# ICAN-7006-MCU.net
KiCad netlist of a schematic drawn in Altium Designer
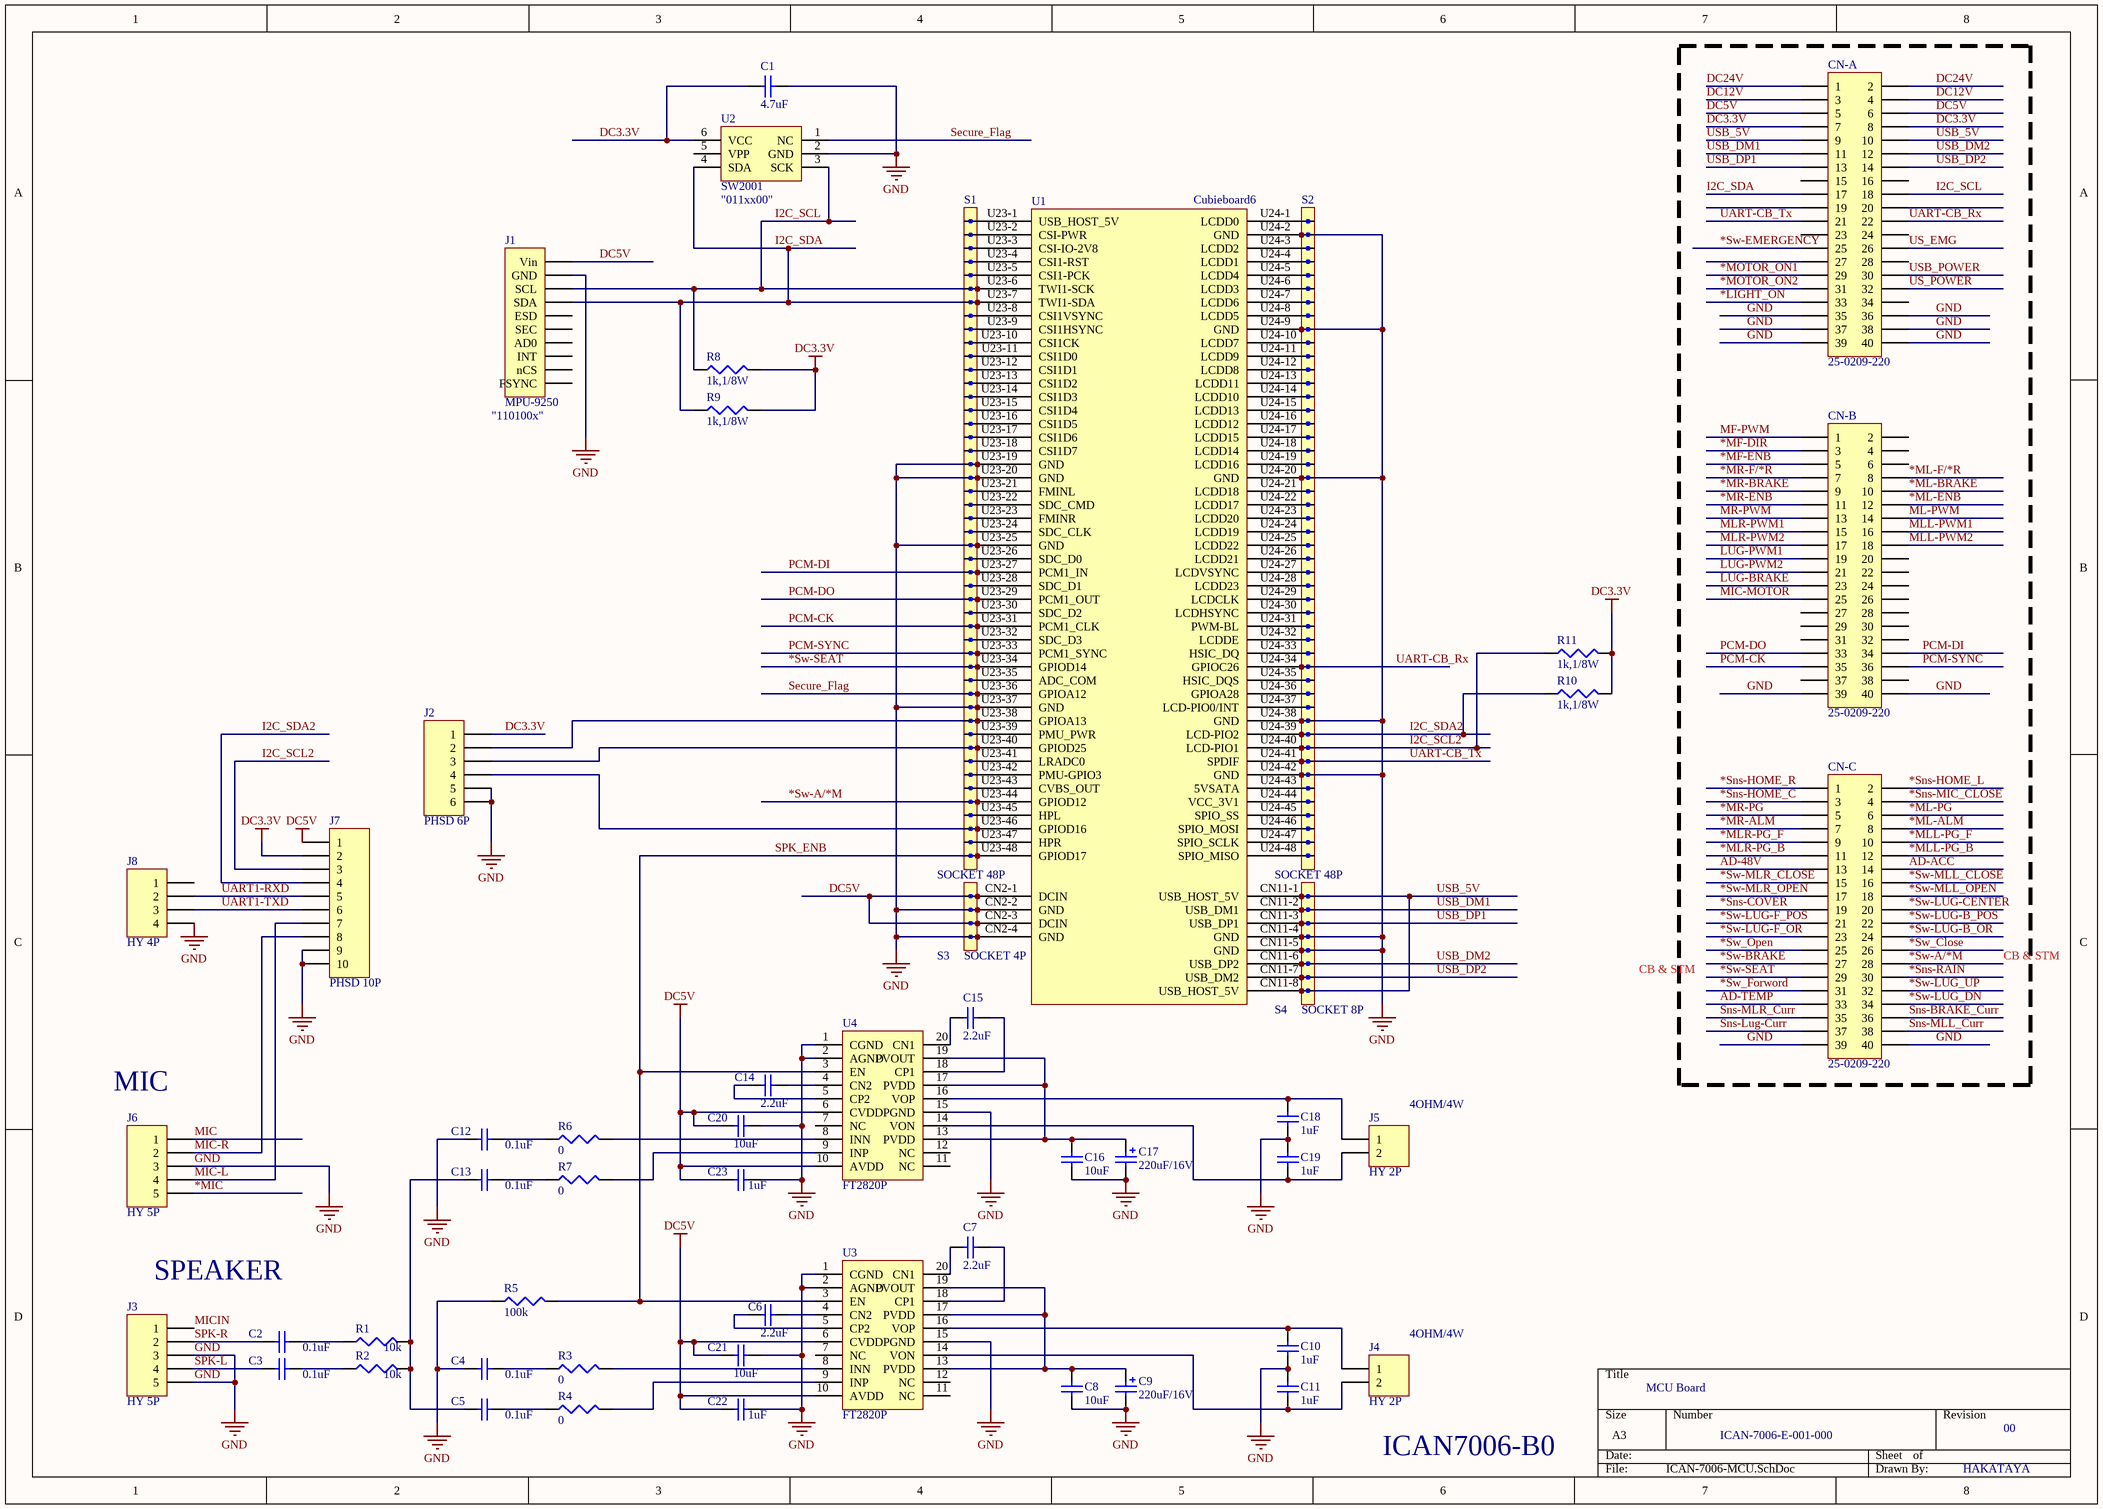
[diagram p0: ICAN-7006-MCU.SchDoc]

(export (version "E")
  (design (tool "Eeschema 10.0.6"))
  (components
    (comp (ref "C1")
      (value "4.7uF")
      (footprint "HAKATAYA:[0805]2012")
      (description "Capacitor")
      (fields (field (name "PUBLISHER") "Altium Limited"))
      (libsource (lib "Miscellaneous Devices") (part "Cap"))
    )
    (comp (ref "C2")
      (value "0.1uF")
      (footprint "[0805]2012")
      (description "Capacitor")
      (fields (field (name "PUBLISHER") "Altium Limited"))
      (libsource (lib "Miscellaneous Devices") (part "Cap Semi"))
    )
    (comp (ref "C3")
      (value "0.1uF")
      (footprint "[0805]2012")
      (description "Capacitor")
      (fields (field (name "PUBLISHER") "Altium Limited"))
      (libsource (lib "Miscellaneous Devices") (part "Cap Semi"))
    )
    (comp (ref "C4")
      (value "0.1uF")
      (footprint "[0805]2012")
      (description "Capacitor")
      (fields (field (name "PUBLISHER") "Altium Limited"))
      (libsource (lib "Miscellaneous Devices") (part "Cap Semi"))
    )
    (comp (ref "C5")
      (value "0.1uF")
      (footprint "[0805]2012")
      (description "Capacitor")
      (fields (field (name "PUBLISHER") "Altium Limited"))
      (libsource (lib "Miscellaneous Devices") (part "Cap Semi"))
    )
    (comp (ref "C6")
      (value "2.2uF")
      (footprint "[0805]2012")
      (description "Capacitor")
      (fields (field (name "PUBLISHER") "Altium Limited"))
      (libsource (lib "Miscellaneous Devices") (part "Cap Semi"))
    )
    (comp (ref "C7")
      (value "2.2uF")
      (footprint "[0805]2012")
      (description "Capacitor")
      (fields (field (name "PUBLISHER") "Altium Limited"))
      (libsource (lib "Miscellaneous Devices") (part "Cap Semi"))
    )
    (comp (ref "C8")
      (value "10uF")
      (footprint "[0805]2012")
      (description "Capacitor")
      (fields (field (name "PUBLISHER") "Altium Limited"))
      (libsource (lib "Miscellaneous Devices") (part "Cap Semi"))
    )
    (comp (ref "C9")
      (value "220uF/16V")
      (footprint "HAKATAYA:CAPA WXA PITCH 3.5mm")
      (description "Polarized Capacitor (Axial)")
      (fields (field (name "PUBLISHER") "Altium Limited"))
      (libsource (lib "Miscellaneous Devices") (part "Cap Pol2"))
    )
    (comp (ref "C10")
      (value "1uF")
      (footprint "[0805]2012")
      (description "Capacitor")
      (fields (field (name "PUBLISHER") "Altium Limited"))
      (libsource (lib "Miscellaneous Devices") (part "Cap Semi"))
    )
    (comp (ref "C11")
      (value "1uF")
      (footprint "[0805]2012")
      (description "Capacitor")
      (fields (field (name "PUBLISHER") "Altium Limited"))
      (libsource (lib "Miscellaneous Devices") (part "Cap Semi"))
    )
    (comp (ref "C12")
      (value "0.1uF")
      (footprint "[0805]2012")
      (description "Capacitor")
      (fields (field (name "PUBLISHER") "Altium Limited"))
      (libsource (lib "Miscellaneous Devices") (part "Cap Semi"))
    )
    (comp (ref "C13")
      (value "0.1uF")
      (footprint "[0805]2012")
      (description "Capacitor")
      (fields (field (name "PUBLISHER") "Altium Limited"))
      (libsource (lib "Miscellaneous Devices") (part "Cap Semi"))
    )
    (comp (ref "C14")
      (value "2.2uF")
      (footprint "[0805]2012")
      (description "Capacitor")
      (fields (field (name "PUBLISHER") "Altium Limited"))
      (libsource (lib "Miscellaneous Devices") (part "Cap Semi"))
    )
    (comp (ref "C15")
      (value "2.2uF")
      (footprint "[0805]2012")
      (description "Capacitor")
      (fields (field (name "PUBLISHER") "Altium Limited"))
      (libsource (lib "Miscellaneous Devices") (part "Cap Semi"))
    )
    (comp (ref "C16")
      (value "10uF")
      (footprint "[0805]2012")
      (description "Capacitor")
      (fields (field (name "PUBLISHER") "Altium Limited"))
      (libsource (lib "Miscellaneous Devices") (part "Cap Semi"))
    )
    (comp (ref "C17")
      (value "220uF/16V")
      (footprint "HAKATAYA:CAPA WXA PITCH 3.5mm")
      (description "Polarized Capacitor (Axial)")
      (fields (field (name "PUBLISHER") "Altium Limited"))
      (libsource (lib "Miscellaneous Devices") (part "Cap Pol2"))
    )
    (comp (ref "C18")
      (value "1uF")
      (footprint "[0805]2012")
      (description "Capacitor")
      (fields (field (name "PUBLISHER") "Altium Limited"))
      (libsource (lib "Miscellaneous Devices") (part "Cap Semi"))
    )
    (comp (ref "C19")
      (value "1uF")
      (footprint "[0805]2012")
      (description "Capacitor")
      (fields (field (name "PUBLISHER") "Altium Limited"))
      (libsource (lib "Miscellaneous Devices") (part "Cap Semi"))
    )
    (comp (ref "C20")
      (value "10uF")
      (footprint "[0805]2012")
      (description "Capacitor")
      (fields (field (name "PUBLISHER") "Altium Limited"))
      (libsource (lib "Miscellaneous Devices") (part "Cap Semi"))
    )
    (comp (ref "C21")
      (value "10uF")
      (footprint "[0805]2012")
      (description "Capacitor")
      (fields (field (name "PUBLISHER") "Altium Limited"))
      (libsource (lib "Miscellaneous Devices") (part "Cap Semi"))
    )
    (comp (ref "C22")
      (value "1uF")
      (footprint "[0805]2012")
      (description "Capacitor")
      (fields (field (name "PUBLISHER") "Altium Limited"))
      (libsource (lib "Miscellaneous Devices") (part "Cap Semi"))
    )
    (comp (ref "C23")
      (value "1uF")
      (footprint "[0805]2012")
      (description "Capacitor")
      (fields (field (name "PUBLISHER") "Altium Limited"))
      (libsource (lib "Miscellaneous Devices") (part "Cap Semi"))
    )
    (comp (ref "CN-A")
      (value "25-0209-220")
      (footprint "HDR2X20")
      (description "Header, 20-Pin, Dual row")
      (fields (field (name "PUBLISHER") "Altium Limited"))
      (libsource (lib "Miscellaneous Connectors") (part "Header 20X2"))
    )
    (comp (ref "CN-B")
      (value "25-0209-220")
      (footprint "HDR2X20")
      (description "Header, 20-Pin, Dual row")
      (fields (field (name "PUBLISHER") "Altium Limited"))
      (libsource (lib "Miscellaneous Connectors") (part "Header 20X2"))
    )
    (comp (ref "CN-C")
      (value "25-0209-220")
      (footprint "HDR2X20")
      (description "Header, 20-Pin, Dual row")
      (fields (field (name "PUBLISHER") "Altium Limited"))
      (libsource (lib "Miscellaneous Connectors") (part "Header 20X2"))
    )
    (comp (ref "J1")
      (value "MPU-9250")
      (footprint "HDR1X10")
      (description "GYRO")
      (fields (field (name "PUBLISHER") "Altium Limited"))
      (libsource (lib "Miscellaneous Connectors") (part "Header 10"))
    )
    (comp (ref "J2")
      (value "PHSD 6P")
      (footprint "HAKATAYA:PHSD WV03x2")
      (description "Header, 6-Pin")
      (fields (field (name "PUBLISHER") "Altium Limited"))
      (libsource (lib "Miscellaneous Connectors") (part "Header 6"))
    )
    (comp (ref "J3")
      (value "HY 5P")
      (footprint "HAKATAYA:HY-5A")
      (description "Header, 5-Pin")
      (fields (field (name "PUBLISHER") "Altium Limited"))
      (libsource (lib "Miscellaneous Connectors") (part "Header 5"))
    )
    (comp (ref "J4")
      (value "HY 2P")
      (footprint "HAKATAYA:HY-2A")
      (description "Header, 2-Pin")
      (fields (field (name "PUBLISHER") "Altium Limited"))
      (libsource (lib "Miscellaneous Connectors") (part "Header 2"))
    )
    (comp (ref "J5")
      (value "HY 2P")
      (footprint "HAKATAYA:HY-2A")
      (description "Header, 2-Pin")
      (fields (field (name "PUBLISHER") "Altium Limited"))
      (libsource (lib "Miscellaneous Connectors") (part "Header 2"))
    )
    (comp (ref "J6")
      (value "HY 5P")
      (footprint "HAKATAYA:HY-5A")
      (description "Header, 5-Pin")
      (fields (field (name "PUBLISHER") "Altium Limited"))
      (libsource (lib "Miscellaneous Connectors") (part "Header 5"))
    )
    (comp (ref "J7")
      (value "PHSD 10P")
      (footprint "HAKATAYA:PHSD WV05x2")
      (description "Header, 10-Pin")
      (fields (field (name "PUBLISHER") "Altium Limited"))
      (libsource (lib "") (part "Header 10_1"))
    )
    (comp (ref "J8")
      (value "HY 4P")
      (footprint "HAKATAYA:HY-4AW")
      (description "Header, 4-Pin")
      (fields (field (name "PUBLISHER") "Altium Limited"))
      (libsource (lib "Miscellaneous Connectors") (part "Header 4"))
    )
    (comp (ref "R1")
      (value "10k")
      (footprint "[0805]2012")
      (description "Resistor")
      (fields (field (name "PUBLISHER") "Altium Limited"))
      (libsource (lib "Miscellaneous Devices") (part "Res3"))
    )
    (comp (ref "R2")
      (value "10k")
      (footprint "[0805]2012")
      (description "Resistor")
      (fields (field (name "PUBLISHER") "Altium Limited"))
      (libsource (lib "Miscellaneous Devices") (part "Res3"))
    )
    (comp (ref "R3")
      (value "0")
      (footprint "[0805]2012")
      (description "Resistor")
      (fields (field (name "PUBLISHER") "Altium Limited"))
      (libsource (lib "Miscellaneous Devices") (part "Res3"))
    )
    (comp (ref "R4")
      (value "0")
      (footprint "[0805]2012")
      (description "Resistor")
      (fields (field (name "PUBLISHER") "Altium Limited"))
      (libsource (lib "Miscellaneous Devices") (part "Res3"))
    )
    (comp (ref "R5")
      (value "100k")
      (footprint "[0805]2012")
      (description "Resistor")
      (fields (field (name "PUBLISHER") "Altium Limited"))
      (libsource (lib "Miscellaneous Devices") (part "Res3"))
    )
    (comp (ref "R6")
      (value "0")
      (footprint "[0805]2012")
      (description "Resistor")
      (fields (field (name "PUBLISHER") "Altium Limited"))
      (libsource (lib "Miscellaneous Devices") (part "Res3"))
    )
    (comp (ref "R7")
      (value "0")
      (footprint "[0805]2012")
      (description "Resistor")
      (fields (field (name "PUBLISHER") "Altium Limited"))
      (libsource (lib "Miscellaneous Devices") (part "Res3"))
    )
    (comp (ref "R8")
      (value "1k,1/8W")
      (footprint "[0805]2012")
      (description "Resistor")
      (fields (field (name "PUBLISHER") "Altium Limited"))
      (libsource (lib "Miscellaneous Devices") (part "Res3"))
    )
    (comp (ref "R9")
      (value "1k,1/8W")
      (footprint "[0805]2012")
      (description "Resistor")
      (fields (field (name "PUBLISHER") "Altium Limited"))
      (libsource (lib "Miscellaneous Devices") (part "Res3"))
    )
    (comp (ref "R10")
      (value "1k,1/8W")
      (footprint "[0805]2012")
      (description "Resistor")
      (fields (field (name "PUBLISHER") "Altium Limited"))
      (libsource (lib "Miscellaneous Devices") (part "Res3"))
    )
    (comp (ref "R11")
      (value "1k,1/8W")
      (footprint "[0805]2012")
      (description "Resistor")
      (fields (field (name "PUBLISHER") "Altium Limited"))
      (libsource (lib "Miscellaneous Devices") (part "Res3"))
    )
    (comp (ref "S1")
      (value "SOCKET 48P")
      (footprint "HAKATAYA:SOCKET 2.0mm X 24 DOUBLE")
      (description "SOCKET")
      (libsource (lib "HAKATAYA") (part "SOCKET 48P"))
    )
    (comp (ref "S2")
      (value "SOCKET 48P")
      (footprint "HAKATAYA:SOCKET 2.0mm X 24 DOUBLE")
      (description "SOCKET")
      (libsource (lib "HAKATAYA") (part "SOCKET 48P"))
    )
    (comp (ref "S3")
      (value "SOCKET 4P")
      (footprint "HAKATAYA:SOCKET 2.0mm X 2 DOUBLE")
      (description "SOCKET")
      (libsource (lib "*") (part "SOCKET 4P"))
    )
    (comp (ref "S4")
      (value "SOCKET 8P")
      (footprint "HAKATAYA:SOCKET 2.0mm X 4 DOUBLE-2")
      (description "SOCKET")
      (libsource (lib "*") (part "SOCKET 8P"))
    )
    (comp (ref "U1")
      (value "Cubieboard6")
      (footprint "HAKATAYA:Cubieboard6")
      (description "MCU")
      (libsource (lib "HAKATAYA") (part "Cubieboard6"))
    )
    (comp (ref "U2")
      (value "SW2001")
      (footprint "HAKATAYA:SOP")
      (description "Secure IC")
      (libsource (lib "HAKATAYA") (part "IC6-WIDE"))
    )
    (comp (ref "U3")
      (value "FT2820P")
      (footprint "SSOP-20")
      (description "Amplifier")
      (libsource (lib "HAKATAYA") (part "IC20"))
    )
    (comp (ref "U4")
      (value "FT2820P")
      (footprint "SSOP-20")
      (description "Amplifier")
      (libsource (lib "HAKATAYA") (part "IC20"))
    )
  )
  (nets
    (net (code "1") (name "/*LIGHT_ON") (class "Default")
      (node (ref "CN-A") (pin "33") (pinfunction "33_33") (pintype "passive"))
    )
    (net (code "2") (name "/*MF-DIR") (class "Default")
      (node (ref "CN-B") (pin "3") (pinfunction "3_3") (pintype "passive"))
    )
    (net (code "3") (name "/*MF-ENB") (class "Default")
      (node (ref "CN-B") (pin "5") (pinfunction "5_5") (pintype "passive"))
    )
    (net (code "4") (name "/*MIC") (class "Default")
      (node (ref "J6") (pin "5") (pinfunction "5_5") (pintype "passive"))
    )
    (net (code "5") (name "/*ML-ALM") (class "Default")
      (node (ref "CN-C") (pin "8") (pinfunction "8_8") (pintype "passive"))
    )
    (net (code "6") (name "/*ML-BRAKE") (class "Default")
      (node (ref "CN-B") (pin "10") (pinfunction "10_10") (pintype "passive"))
    )
    (net (code "7") (name "/*ML-ENB") (class "Default")
      (node (ref "CN-B") (pin "12") (pinfunction "12_12") (pintype "passive"))
    )
    (net (code "8") (name "/*ML-F{slash}*R") (class "Default")
      (node (ref "CN-B") (pin "8") (pinfunction "8_8") (pintype "passive"))
    )
    (net (code "9") (name "/*ML-PG") (class "Default")
      (node (ref "CN-C") (pin "6") (pinfunction "6_6") (pintype "passive"))
    )
    (net (code "10") (name "/*MLL-PG_B") (class "Default")
      (node (ref "CN-C") (pin "12") (pinfunction "12_12") (pintype "passive"))
    )
    (net (code "11") (name "/*MLL-PG_F") (class "Default")
      (node (ref "CN-C") (pin "10") (pinfunction "10_10") (pintype "passive"))
    )
    (net (code "12") (name "/*MLR-PG_B") (class "Default")
      (node (ref "CN-C") (pin "11") (pinfunction "11_11") (pintype "passive"))
    )
    (net (code "13") (name "/*MLR-PG_F") (class "Default")
      (node (ref "CN-C") (pin "9") (pinfunction "9_9") (pintype "passive"))
    )
    (net (code "14") (name "/*MOTOR_ON1") (class "Default")
      (node (ref "CN-A") (pin "29") (pinfunction "29_29") (pintype "passive"))
    )
    (net (code "15") (name "/*MOTOR_ON2") (class "Default")
      (node (ref "CN-A") (pin "31") (pinfunction "31_31") (pintype "passive"))
    )
    (net (code "16") (name "/*MR-ALM") (class "Default")
      (node (ref "CN-C") (pin "7") (pinfunction "7_7") (pintype "passive"))
    )
    (net (code "17") (name "/*MR-BRAKE") (class "Default")
      (node (ref "CN-B") (pin "9") (pinfunction "9_9") (pintype "passive"))
    )
    (net (code "18") (name "/*MR-ENB") (class "Default")
      (node (ref "CN-B") (pin "11") (pinfunction "11_11") (pintype "passive"))
    )
    (net (code "19") (name "/*MR-F{slash}*R") (class "Default")
      (node (ref "CN-B") (pin "7") (pinfunction "7_7") (pintype "passive"))
    )
    (net (code "20") (name "/*MR-PG") (class "Default")
      (node (ref "CN-C") (pin "5") (pinfunction "5_5") (pintype "passive"))
    )
    (net (code "21") (name "/*Sns-COVER") (class "Default")
      (node (ref "CN-C") (pin "19") (pinfunction "19_19") (pintype "passive"))
    )
    (net (code "22") (name "/*Sns-HOME_C") (class "Default")
      (node (ref "CN-C") (pin "3") (pinfunction "3_3") (pintype "passive"))
    )
    (net (code "23") (name "/*Sns-HOME_L") (class "Default")
      (node (ref "CN-C") (pin "2") (pinfunction "2_2") (pintype "passive"))
    )
    (net (code "24") (name "/*Sns-HOME_R") (class "Default")
      (node (ref "CN-C") (pin "1") (pinfunction "1_1") (pintype "passive"))
    )
    (net (code "25") (name "/*Sns-MIC_CLOSE") (class "Default")
      (node (ref "CN-C") (pin "4") (pinfunction "4_4") (pintype "passive"))
    )
    (net (code "26") (name "/*Sns-RAIN") (class "Default")
      (node (ref "CN-C") (pin "30") (pinfunction "30_30") (pintype "passive"))
    )
    (net (code "27") (name "/*Sw-A{slash}*M") (class "Default")
      (node (ref "CN-C") (pin "28") (pinfunction "28_28") (pintype "passive"))
      (node (ref "S1") (pin "44") (pinfunction "44_44") (pintype "passive"))
      (node (ref "U1") (pin "U23-44") (pinfunction "GPIOD12_U23-44") (pintype "passive"))
    )
    (net (code "28") (name "/*Sw-BRAKE") (class "Default")
      (node (ref "CN-C") (pin "27") (pinfunction "27_27") (pintype "passive"))
    )
    (net (code "29") (name "/*Sw-EMERGENCY") (class "Default")
      (node (ref "CN-A") (pin "25") (pinfunction "25_25") (pintype "passive"))
    )
    (net (code "30") (name "/*Sw-LUG-B_OR") (class "Default")
      (node (ref "CN-C") (pin "24") (pinfunction "24_24") (pintype "passive"))
    )
    (net (code "31") (name "/*Sw-LUG-B_POS") (class "Default")
      (node (ref "CN-C") (pin "22") (pinfunction "22_22") (pintype "passive"))
    )
    (net (code "32") (name "/*Sw-LUG-CENTER") (class "Default")
      (node (ref "CN-C") (pin "20") (pinfunction "20_20") (pintype "passive"))
    )
    (net (code "33") (name "/*Sw-LUG-F_OR") (class "Default")
      (node (ref "CN-C") (pin "23") (pinfunction "23_23") (pintype "passive"))
    )
    (net (code "34") (name "/*Sw-LUG-F_POS") (class "Default")
      (node (ref "CN-C") (pin "21") (pinfunction "21_21") (pintype "passive"))
    )
    (net (code "35") (name "/*Sw-LUG_DN") (class "Default")
      (node (ref "CN-C") (pin "34") (pinfunction "34_34") (pintype "passive"))
    )
    (net (code "36") (name "/*Sw-LUG_UP") (class "Default")
      (node (ref "CN-C") (pin "32") (pinfunction "32_32") (pintype "passive"))
    )
    (net (code "37") (name "/*Sw-MLL_CLOSE") (class "Default")
      (node (ref "CN-C") (pin "16") (pinfunction "16_16") (pintype "passive"))
    )
    (net (code "38") (name "/*Sw-MLL_OPEN") (class "Default")
      (node (ref "CN-C") (pin "18") (pinfunction "18_18") (pintype "passive"))
    )
    (net (code "39") (name "/*Sw-MLR_CLOSE") (class "Default")
      (node (ref "CN-C") (pin "15") (pinfunction "15_15") (pintype "passive"))
    )
    (net (code "40") (name "/*Sw-MLR_OPEN") (class "Default")
      (node (ref "CN-C") (pin "17") (pinfunction "17_17") (pintype "passive"))
    )
    (net (code "41") (name "/*Sw-SEAT") (class "Default")
      (node (ref "CN-C") (pin "29") (pinfunction "29_29") (pintype "passive"))
      (node (ref "S1") (pin "34") (pinfunction "34_34") (pintype "passive"))
      (node (ref "U1") (pin "U23-34") (pinfunction "GPIOD14_U23-34") (pintype "passive"))
    )
    (net (code "42") (name "/*Sw_Close") (class "Default")
      (node (ref "CN-C") (pin "26") (pinfunction "26_26") (pintype "passive"))
    )
    (net (code "43") (name "/*Sw_Forword") (class "Default")
      (node (ref "CN-C") (pin "31") (pinfunction "31_31") (pintype "passive"))
    )
    (net (code "44") (name "/*Sw_Open") (class "Default")
      (node (ref "CN-C") (pin "25") (pinfunction "25_25") (pintype "passive"))
    )
    (net (code "45") (name "/AD-48V") (class "Default")
      (node (ref "CN-C") (pin "13") (pinfunction "13_13") (pintype "passive"))
    )
    (net (code "46") (name "/AD-ACC") (class "Default")
      (node (ref "CN-C") (pin "14") (pinfunction "14_14") (pintype "passive"))
    )
    (net (code "47") (name "/AD-TEMP") (class "Default")
      (node (ref "CN-C") (pin "33") (pinfunction "33_33") (pintype "passive"))
    )
    (net (code "48") (name "/DC12V") (class "Default")
      (node (ref "CN-A") (pin "3") (pinfunction "3_3") (pintype "passive"))
      (node (ref "CN-A") (pin "4") (pinfunction "4_4") (pintype "passive"))
    )
    (net (code "49") (name "/DC24V") (class "Default")
      (node (ref "CN-A") (pin "1") (pinfunction "1_1") (pintype "passive"))
      (node (ref "CN-A") (pin "2") (pinfunction "2_2") (pintype "passive"))
    )
    (net (code "50") (name "/I2C_SCL") (class "Default")
      (node (ref "CN-A") (pin "18") (pinfunction "18_18") (pintype "passive"))
      (node (ref "J1") (pin "3") (pinfunction "SCL_3") (pintype "passive"))
      (node (ref "R8") (pin "1") (pinfunction "1_1") (pintype "passive"))
      (node (ref "S1") (pin "6") (pinfunction "6_6") (pintype "passive"))
      (node (ref "U1") (pin "U23-6") (pinfunction "TWI1-SCK_U23-6") (pintype "passive"))
      (node (ref "U2") (pin "3") (pinfunction "SCK_3") (pintype "passive"))
    )
    (net (code "51") (name "/I2C_SCL2") (class "Default")
      (node (ref "J7") (pin "3") (pinfunction "3_3") (pintype "passive"))
      (node (ref "R11") (pin "1") (pinfunction "1_1") (pintype "passive"))
      (node (ref "S2") (pin "40") (pinfunction "40_40") (pintype "passive"))
      (node (ref "U1") (pin "U24-40") (pinfunction "LCD-PIO1_U24-40") (pintype "passive"))
    )
    (net (code "52") (name "/I2C_SDA") (class "Default")
      (node (ref "CN-A") (pin "17") (pinfunction "17_17") (pintype "passive"))
      (node (ref "J1") (pin "4") (pinfunction "SDA_4") (pintype "passive"))
      (node (ref "R9") (pin "1") (pinfunction "1_1") (pintype "passive"))
      (node (ref "S1") (pin "7") (pinfunction "7_7") (pintype "passive"))
      (node (ref "U1") (pin "U23-7") (pinfunction "TWI1-SDA_U23-7") (pintype "passive"))
      (node (ref "U2") (pin "4") (pinfunction "SDA_4") (pintype "passive"))
    )
    (net (code "53") (name "/I2C_SDA2") (class "Default")
      (node (ref "J7") (pin "4") (pinfunction "4_4") (pintype "passive"))
      (node (ref "R10") (pin "1") (pinfunction "1_1") (pintype "passive"))
      (node (ref "S2") (pin "39") (pinfunction "39_39") (pintype "passive"))
      (node (ref "U1") (pin "U24-39") (pinfunction "LCD-PIO2_U24-39") (pintype "passive"))
    )
    (net (code "54") (name "/LUG-BRAKE") (class "Default")
      (node (ref "CN-B") (pin "23") (pinfunction "23_23") (pintype "passive"))
    )
    (net (code "55") (name "/LUG-PWM1") (class "Default")
      (node (ref "CN-B") (pin "19") (pinfunction "19_19") (pintype "passive"))
    )
    (net (code "56") (name "/LUG-PWM2") (class "Default")
      (node (ref "CN-B") (pin "21") (pinfunction "21_21") (pintype "passive"))
    )
    (net (code "57") (name "/MF-PWM") (class "Default")
      (node (ref "CN-B") (pin "1") (pinfunction "1_1") (pintype "passive"))
    )
    (net (code "58") (name "/MIC") (class "Default")
      (node (ref "J6") (pin "1") (pinfunction "1_1") (pintype "passive"))
    )
    (net (code "59") (name "/MIC-L") (class "Default")
      (node (ref "J6") (pin "4") (pinfunction "4_4") (pintype "passive"))
      (node (ref "J7") (pin "7") (pinfunction "7_7") (pintype "passive"))
    )
    (net (code "60") (name "/MIC-MOTOR") (class "Default")
      (node (ref "CN-B") (pin "25") (pinfunction "25_25") (pintype "passive"))
    )
    (net (code "61") (name "/MIC-R") (class "Default")
      (node (ref "J6") (pin "2") (pinfunction "2_2") (pintype "passive"))
      (node (ref "J7") (pin "8") (pinfunction "8_8") (pintype "passive"))
    )
    (net (code "62") (name "/MICIN") (class "Default")
      (node (ref "J3") (pin "1") (pinfunction "1_1") (pintype "passive"))
    )
    (net (code "63") (name "/ML-PWM") (class "Default")
      (node (ref "CN-B") (pin "14") (pinfunction "14_14") (pintype "passive"))
    )
    (net (code "64") (name "/MLL-PWM1") (class "Default")
      (node (ref "CN-B") (pin "16") (pinfunction "16_16") (pintype "passive"))
    )
    (net (code "65") (name "/MLL-PWM2") (class "Default")
      (node (ref "CN-B") (pin "18") (pinfunction "18_18") (pintype "passive"))
    )
    (net (code "66") (name "/MLR-PWM1") (class "Default")
      (node (ref "CN-B") (pin "15") (pinfunction "15_15") (pintype "passive"))
    )
    (net (code "67") (name "/MLR-PWM2") (class "Default")
      (node (ref "CN-B") (pin "17") (pinfunction "17_17") (pintype "passive"))
    )
    (net (code "68") (name "/MR-PWM") (class "Default")
      (node (ref "CN-B") (pin "13") (pinfunction "13_13") (pintype "passive"))
    )
    (net (code "69") (name "/PCM-CK") (class "Default")
      (node (ref "CN-B") (pin "35") (pinfunction "35_35") (pintype "passive"))
      (node (ref "S1") (pin "31") (pinfunction "31_31") (pintype "passive"))
      (node (ref "U1") (pin "U23-31") (pinfunction "PCM1_CLK_U23-31") (pintype "passive"))
    )
    (net (code "70") (name "/PCM-DI") (class "Default")
      (node (ref "CN-B") (pin "34") (pinfunction "34_34") (pintype "passive"))
      (node (ref "S1") (pin "27") (pinfunction "27_27") (pintype "passive"))
      (node (ref "U1") (pin "U23-27") (pinfunction "PCM1_IN_U23-27") (pintype "passive"))
    )
    (net (code "71") (name "/PCM-DO") (class "Default")
      (node (ref "CN-B") (pin "33") (pinfunction "33_33") (pintype "passive"))
      (node (ref "S1") (pin "29") (pinfunction "29_29") (pintype "passive"))
      (node (ref "U1") (pin "U23-29") (pinfunction "PCM1_OUT_U23-29") (pintype "passive"))
    )
    (net (code "72") (name "/PCM-SYNC") (class "Default")
      (node (ref "CN-B") (pin "36") (pinfunction "36_36") (pintype "passive"))
      (node (ref "S1") (pin "33") (pinfunction "33_33") (pintype "passive"))
      (node (ref "U1") (pin "U23-33") (pinfunction "PCM1_SYNC_U23-33") (pintype "passive"))
    )
    (net (code "73") (name "/SPK-L") (class "Default")
      (node (ref "C3") (pin "1") (pinfunction "1_1") (pintype "passive"))
      (node (ref "J3") (pin "4") (pinfunction "4_4") (pintype "passive"))
    )
    (net (code "74") (name "/SPK-R") (class "Default")
      (node (ref "C2") (pin "1") (pinfunction "1_1") (pintype "passive"))
      (node (ref "J3") (pin "2") (pinfunction "2_2") (pintype "passive"))
    )
    (net (code "75") (name "/SPK_ENB") (class "Default")
      (node (ref "R5") (pin "1") (pinfunction "1_1") (pintype "passive"))
      (node (ref "S1") (pin "48") (pinfunction "48_48") (pintype "passive"))
      (node (ref "U1") (pin "U23-48") (pinfunction "GPIOD17_U23-48") (pintype "passive"))
      (node (ref "U3") (pin "3") (pinfunction "EN_3") (pintype "passive"))
      (node (ref "U4") (pin "3") (pinfunction "EN_3") (pintype "passive"))
    )
    (net (code "76") (name "/Secure_Flag") (class "Default")
      (node (ref "S1") (pin "36") (pinfunction "36_36") (pintype "passive"))
      (node (ref "U1") (pin "U23-36") (pinfunction "GPIOA12_U23-36") (pintype "passive"))
      (node (ref "U2") (pin "1") (pinfunction "NC_1") (pintype "passive"))
    )
    (net (code "77") (name "/Sns-BRAKE_Curr") (class "Default")
      (node (ref "CN-C") (pin "36") (pinfunction "36_36") (pintype "passive"))
    )
    (net (code "78") (name "/Sns-Lug-Curr") (class "Default")
      (node (ref "CN-C") (pin "37") (pinfunction "37_37") (pintype "passive"))
    )
    (net (code "79") (name "/Sns-MLL_Curr") (class "Default")
      (node (ref "CN-C") (pin "38") (pinfunction "38_38") (pintype "passive"))
    )
    (net (code "80") (name "/Sns-MLR_Curr") (class "Default")
      (node (ref "CN-C") (pin "35") (pinfunction "35_35") (pintype "passive"))
    )
    (net (code "81") (name "/UART-CB_Rx") (class "Default")
      (node (ref "CN-A") (pin "22") (pinfunction "22_22") (pintype "passive"))
      (node (ref "S2") (pin "34") (pinfunction "34_34") (pintype "passive"))
      (node (ref "U1") (pin "U24-34") (pinfunction "GPIOC26_U24-34") (pintype "passive"))
    )
    (net (code "82") (name "/UART-CB_Tx") (class "Default")
      (node (ref "CN-A") (pin "21") (pinfunction "21_21") (pintype "passive"))
      (node (ref "S2") (pin "41") (pinfunction "41_41") (pintype "passive"))
      (node (ref "U1") (pin "U24-41") (pinfunction "SPDIF_U24-41") (pintype "passive"))
    )
    (net (code "83") (name "/UART1-RXD") (class "Default")
      (node (ref "J7") (pin "5") (pinfunction "5_5") (pintype "passive"))
      (node (ref "J8") (pin "2") (pinfunction "2_2") (pintype "passive"))
    )
    (net (code "84") (name "/UART1-TXD") (class "Default")
      (node (ref "J7") (pin "6") (pinfunction "6_6") (pintype "passive"))
      (node (ref "J8") (pin "3") (pinfunction "3_3") (pintype "passive"))
    )
    (net (code "85") (name "/USB_5V") (class "Default")
      (node (ref "CN-A") (pin "10") (pinfunction "10_10") (pintype "passive"))
      (node (ref "CN-A") (pin "9") (pinfunction "9_9") (pintype "passive"))
      (node (ref "S4") (pin "1") (pinfunction "1_1") (pintype "passive"))
      (node (ref "S4") (pin "8") (pinfunction "8_8") (pintype "passive"))
      (node (ref "U1") (pin "CN11-1") (pinfunction "USB_HOST_5V_CN11-1") (pintype "passive"))
      (node (ref "U1") (pin "CN11-8") (pinfunction "USB_HOST_5V_CN11-8") (pintype "passive"))
    )
    (net (code "86") (name "/USB_DM1") (class "Default")
      (node (ref "CN-A") (pin "11") (pinfunction "11_11") (pintype "passive"))
      (node (ref "S4") (pin "2") (pinfunction "2_2") (pintype "passive"))
      (node (ref "U1") (pin "CN11-2") (pinfunction "USB_DM1_CN11-2") (pintype "passive"))
    )
    (net (code "87") (name "/USB_DM2") (class "Default")
      (node (ref "CN-A") (pin "12") (pinfunction "12_12") (pintype "passive"))
      (node (ref "S4") (pin "6") (pinfunction "6_6") (pintype "passive"))
      (node (ref "U1") (pin "CN11-6") (pinfunction "USB_DP2_CN11-6") (pintype "passive"))
    )
    (net (code "88") (name "/USB_DP1") (class "Default")
      (node (ref "CN-A") (pin "13") (pinfunction "13_13") (pintype "passive"))
      (node (ref "S4") (pin "3") (pinfunction "3_3") (pintype "passive"))
      (node (ref "U1") (pin "CN11-3") (pinfunction "USB_DP1_CN11-3") (pintype "passive"))
    )
    (net (code "89") (name "/USB_DP2") (class "Default")
      (node (ref "CN-A") (pin "14") (pinfunction "14_14") (pintype "passive"))
      (node (ref "S4") (pin "7") (pinfunction "7_7") (pintype "passive"))
      (node (ref "U1") (pin "CN11-7") (pinfunction "USB_DM2_CN11-7") (pintype "passive"))
    )
    (net (code "90") (name "/USB_POWER") (class "Default")
      (node (ref "CN-A") (pin "30") (pinfunction "30_30") (pintype "passive"))
    )
    (net (code "91") (name "/US_EMG") (class "Default")
      (node (ref "CN-A") (pin "26") (pinfunction "26_26") (pintype "passive"))
    )
    (net (code "92") (name "/US_POWER") (class "Default")
      (node (ref "CN-A") (pin "32") (pinfunction "32_32") (pintype "passive"))
    )
    (net (code "93") (name "DC3.3V") (class "Default")
      (node (ref "C1") (pin "1") (pinfunction "1_1") (pintype "passive"))
      (node (ref "CN-A") (pin "7") (pinfunction "7_7") (pintype "passive"))
      (node (ref "CN-A") (pin "8") (pinfunction "8_8") (pintype "passive"))
      (node (ref "J2") (pin "1") (pinfunction "1_1") (pintype "passive"))
      (node (ref "J7") (pin "2") (pinfunction "2_2") (pintype "passive"))
      (node (ref "R10") (pin "2") (pinfunction "2_2") (pintype "passive"))
      (node (ref "R11") (pin "2") (pinfunction "2_2") (pintype "passive"))
      (node (ref "R8") (pin "2") (pinfunction "2_2") (pintype "passive"))
      (node (ref "R9") (pin "2") (pinfunction "2_2") (pintype "passive"))
      (node (ref "U2") (pin "6") (pinfunction "VCC_6") (pintype "passive"))
    )
    (net (code "94") (name "DC5V") (class "Default")
      (node (ref "C20") (pin "1") (pinfunction "1_1") (pintype "passive"))
      (node (ref "C21") (pin "1") (pinfunction "1_1") (pintype "passive"))
      (node (ref "C22") (pin "1") (pinfunction "1_1") (pintype "passive"))
      (node (ref "C23") (pin "1") (pinfunction "1_1") (pintype "passive"))
      (node (ref "CN-A") (pin "5") (pinfunction "5_5") (pintype "passive"))
      (node (ref "CN-A") (pin "6") (pinfunction "6_6") (pintype "passive"))
      (node (ref "J1") (pin "1") (pinfunction "Vin_1") (pintype "passive"))
      (node (ref "J7") (pin "1") (pinfunction "1_1") (pintype "passive"))
      (node (ref "S3") (pin "1") (pinfunction "1_1") (pintype "passive"))
      (node (ref "S3") (pin "3") (pinfunction "3_3") (pintype "passive"))
      (node (ref "U1") (pin "CN2-1") (pinfunction "DCIN_CN2-1") (pintype "passive"))
      (node (ref "U1") (pin "CN2-3") (pinfunction "DCIN_CN2-3") (pintype "passive"))
      (node (ref "U3") (pin "10") (pinfunction "AVDD_10") (pintype "passive"))
      (node (ref "U3") (pin "6") (pinfunction "CVDD_6") (pintype "passive"))
      (node (ref "U4") (pin "10") (pinfunction "AVDD_10") (pintype "passive"))
      (node (ref "U4") (pin "6") (pinfunction "CVDD_6") (pintype "passive"))
    )
    (net (code "95") (name "GND") (class "Default")
      (node (ref "C1") (pin "2") (pinfunction "2_2") (pintype "passive"))
      (node (ref "C10") (pin "1") (pinfunction "1_1") (pintype "passive"))
      (node (ref "C11") (pin "2") (pinfunction "2_2") (pintype "passive"))
      (node (ref "C12") (pin "1") (pinfunction "1_1") (pintype "passive"))
      (node (ref "C16") (pin "1") (pinfunction "1_1") (pintype "passive"))
      (node (ref "C17") (pin "2") (pinfunction "2_2") (pintype "passive"))
      (node (ref "C18") (pin "1") (pinfunction "1_1") (pintype "passive"))
      (node (ref "C19") (pin "2") (pinfunction "2_2") (pintype "passive"))
      (node (ref "C20") (pin "2") (pinfunction "2_2") (pintype "passive"))
      (node (ref "C21") (pin "2") (pinfunction "2_2") (pintype "passive"))
      (node (ref "C22") (pin "2") (pinfunction "2_2") (pintype "passive"))
      (node (ref "C23") (pin "2") (pinfunction "2_2") (pintype "passive"))
      (node (ref "C4") (pin "1") (pinfunction "1_1") (pintype "passive"))
      (node (ref "C8") (pin "1") (pinfunction "1_1") (pintype "passive"))
      (node (ref "C9") (pin "2") (pinfunction "2_2") (pintype "passive"))
      (node (ref "CN-A") (pin "35") (pinfunction "35_35") (pintype "passive"))
      (node (ref "CN-A") (pin "36") (pinfunction "36_36") (pintype "passive"))
      (node (ref "CN-A") (pin "37") (pinfunction "37_37") (pintype "passive"))
      (node (ref "CN-A") (pin "38") (pinfunction "38_38") (pintype "passive"))
      (node (ref "CN-A") (pin "39") (pinfunction "39_39") (pintype "passive"))
      (node (ref "CN-A") (pin "40") (pinfunction "40_40") (pintype "passive"))
      (node (ref "CN-B") (pin "39") (pinfunction "39_39") (pintype "passive"))
      (node (ref "CN-B") (pin "40") (pinfunction "40_40") (pintype "passive"))
      (node (ref "CN-C") (pin "39") (pinfunction "39_39") (pintype "passive"))
      (node (ref "CN-C") (pin "40") (pinfunction "40_40") (pintype "passive"))
      (node (ref "J1") (pin "2") (pinfunction "GND_2") (pintype "passive"))
      (node (ref "J2") (pin "5") (pinfunction "5_5") (pintype "passive"))
      (node (ref "J2") (pin "6") (pinfunction "6_6") (pintype "passive"))
      (node (ref "J3") (pin "3") (pinfunction "3_3") (pintype "passive"))
      (node (ref "J3") (pin "5") (pinfunction "5_5") (pintype "passive"))
      (node (ref "J6") (pin "3") (pinfunction "3_3") (pintype "passive"))
      (node (ref "J7") (pin "10") (pinfunction "10_10") (pintype "passive"))
      (node (ref "J7") (pin "9") (pinfunction "9_9") (pintype "passive"))
      (node (ref "J8") (pin "4") (pinfunction "4_4") (pintype "passive"))
      (node (ref "R5") (pin "2") (pinfunction "2_2") (pintype "passive"))
      (node (ref "S1") (pin "19") (pinfunction "19_19") (pintype "passive"))
      (node (ref "S1") (pin "20") (pinfunction "20_20") (pintype "passive"))
      (node (ref "S1") (pin "25") (pinfunction "25_25") (pintype "passive"))
      (node (ref "S1") (pin "37") (pinfunction "37_37") (pintype "passive"))
      (node (ref "S2") (pin "2") (pinfunction "2_2") (pintype "passive"))
      (node (ref "S2") (pin "20") (pinfunction "20_20") (pintype "passive"))
      (node (ref "S2") (pin "38") (pinfunction "38_38") (pintype "passive"))
      (node (ref "S2") (pin "42") (pinfunction "42_42") (pintype "passive"))
      (node (ref "S2") (pin "9") (pinfunction "9_9") (pintype "passive"))
      (node (ref "S3") (pin "2") (pinfunction "2_2") (pintype "passive"))
      (node (ref "S3") (pin "4") (pinfunction "4_4") (pintype "passive"))
      (node (ref "S4") (pin "4") (pinfunction "4_4") (pintype "passive"))
      (node (ref "S4") (pin "5") (pinfunction "5_5") (pintype "passive"))
      (node (ref "U1") (pin "CN11-4") (pinfunction "GND_CN11-4") (pintype "passive"))
      (node (ref "U1") (pin "CN11-5") (pinfunction "GND_CN11-5") (pintype "passive"))
      (node (ref "U1") (pin "CN2-2") (pinfunction "GND_CN2-2") (pintype "passive"))
      (node (ref "U1") (pin "CN2-4") (pinfunction "GND_CN2-4") (pintype "passive"))
      (node (ref "U1") (pin "U23-19") (pinfunction "GND_U23-19") (pintype "passive"))
      (node (ref "U1") (pin "U23-20") (pinfunction "GND_U23-20") (pintype "passive"))
      (node (ref "U1") (pin "U23-25") (pinfunction "GND_U23-25") (pintype "passive"))
      (node (ref "U1") (pin "U23-37") (pinfunction "GND_U23-37") (pintype "passive"))
      (node (ref "U1") (pin "U24-2") (pinfunction "GND_U24-2") (pintype "passive"))
      (node (ref "U1") (pin "U24-20") (pinfunction "GND_U24-20") (pintype "passive"))
      (node (ref "U1") (pin "U24-38") (pinfunction "GND_U24-38") (pintype "passive"))
      (node (ref "U1") (pin "U24-42") (pinfunction "GND_U24-42") (pintype "passive"))
      (node (ref "U1") (pin "U24-9") (pinfunction "GND_U24-9") (pintype "passive"))
      (node (ref "U2") (pin "2") (pinfunction "GND_2") (pintype "passive"))
      (node (ref "U3") (pin "1") (pinfunction "CGND_1") (pintype "passive"))
      (node (ref "U3") (pin "15") (pinfunction "PGND_15") (pintype "passive"))
      (node (ref "U3") (pin "2") (pinfunction "AGND_2") (pintype "passive"))
      (node (ref "U4") (pin "1") (pinfunction "CGND_1") (pintype "passive"))
      (node (ref "U4") (pin "15") (pinfunction "PGND_15") (pintype "passive"))
      (node (ref "U4") (pin "2") (pinfunction "AGND_2") (pintype "passive"))
    )
    (net (code "96") (name "Net-(C2-Pad2)") (class "Default")
      (node (ref "C2") (pin "2") (pinfunction "2_2") (pintype "passive"))
      (node (ref "R1") (pin "1") (pinfunction "1_1") (pintype "passive"))
    )
    (net (code "97") (name "Net-(C3-Pad2)") (class "Default")
      (node (ref "C3") (pin "2") (pinfunction "2_2") (pintype "passive"))
      (node (ref "R2") (pin "1") (pinfunction "1_1") (pintype "passive"))
    )
    (net (code "98") (name "Net-(C4-Pad2)") (class "Default")
      (node (ref "C4") (pin "2") (pinfunction "2_2") (pintype "passive"))
      (node (ref "R3") (pin "1") (pinfunction "1_1") (pintype "passive"))
    )
    (net (code "99") (name "Net-(C5-Pad2)") (class "Default")
      (node (ref "C5") (pin "2") (pinfunction "2_2") (pintype "passive"))
      (node (ref "R4") (pin "1") (pinfunction "1_1") (pintype "passive"))
    )
    (net (code "100") (name "Net-(C12-Pad2)") (class "Default")
      (node (ref "C12") (pin "2") (pinfunction "2_2") (pintype "passive"))
      (node (ref "R6") (pin "1") (pinfunction "1_1") (pintype "passive"))
    )
    (net (code "101") (name "Net-(C13-Pad1)") (class "Default")
      (node (ref "C13") (pin "1") (pinfunction "1_1") (pintype "passive"))
      (node (ref "C5") (pin "1") (pinfunction "1_1") (pintype "passive"))
      (node (ref "R1") (pin "2") (pinfunction "2_2") (pintype "passive"))
      (node (ref "R2") (pin "2") (pinfunction "2_2") (pintype "passive"))
    )
    (net (code "102") (name "Net-(C13-Pad2)") (class "Default")
      (node (ref "C13") (pin "2") (pinfunction "2_2") (pintype "passive"))
      (node (ref "R7") (pin "1") (pinfunction "1_1") (pintype "passive"))
    )
    (net (code "103") (name "Net-(S1-Pad1)") (class "Default")
      (node (ref "S1") (pin "1") (pinfunction "1_1") (pintype "passive"))
      (node (ref "U1") (pin "U23-1") (pinfunction "USB_HOST_5V_U23-1") (pintype "passive"))
    )
    (net (code "104") (name "Net-(U1-5VSATA)") (class "Default")
      (node (ref "S2") (pin "43") (pinfunction "43_43") (pintype "passive"))
      (node (ref "U1") (pin "U24-43") (pinfunction "5VSATA_U24-43") (pintype "passive"))
    )
    (net (code "105") (name "Net-(U1-ADC_COM)") (class "Default")
      (node (ref "S1") (pin "35") (pinfunction "35_35") (pintype "passive"))
      (node (ref "U1") (pin "U23-35") (pinfunction "ADC_COM_U23-35") (pintype "passive"))
    )
    (net (code "106") (name "Net-(U1-CSI-IO-2V8)") (class "Default")
      (node (ref "S1") (pin "3") (pinfunction "3_3") (pintype "passive"))
      (node (ref "U1") (pin "U23-3") (pinfunction "CSI-IO-2V8_U23-3") (pintype "passive"))
    )
    (net (code "107") (name "Net-(U1-CSI-PWR)") (class "Default")
      (node (ref "S1") (pin "2") (pinfunction "2_2") (pintype "passive"))
      (node (ref "U1") (pin "U23-2") (pinfunction "CSI-PWR_U23-2") (pintype "passive"))
    )
    (net (code "108") (name "Net-(U1-CSI1-PCK)") (class "Default")
      (node (ref "S1") (pin "5") (pinfunction "5_5") (pintype "passive"))
      (node (ref "U1") (pin "U23-5") (pinfunction "CSI1-PCK_U23-5") (pintype "passive"))
    )
    (net (code "109") (name "Net-(U1-CSI1-RST)") (class "Default")
      (node (ref "S1") (pin "4") (pinfunction "4_4") (pintype "passive"))
      (node (ref "U1") (pin "U23-4") (pinfunction "CSI1-RST_U23-4") (pintype "passive"))
    )
    (net (code "110") (name "Net-(U1-CSI1CK)") (class "Default")
      (node (ref "S1") (pin "10") (pinfunction "10_10") (pintype "passive"))
      (node (ref "U1") (pin "U23-10") (pinfunction "CSI1CK_U23-10") (pintype "passive"))
    )
    (net (code "111") (name "Net-(U1-CSI1D0)") (class "Default")
      (node (ref "S1") (pin "11") (pinfunction "11_11") (pintype "passive"))
      (node (ref "U1") (pin "U23-11") (pinfunction "CSI1D0_U23-11") (pintype "passive"))
    )
    (net (code "112") (name "Net-(U1-CSI1D1)") (class "Default")
      (node (ref "S1") (pin "12") (pinfunction "12_12") (pintype "passive"))
      (node (ref "U1") (pin "U23-12") (pinfunction "CSI1D1_U23-12") (pintype "passive"))
    )
    (net (code "113") (name "Net-(U1-CSI1D2)") (class "Default")
      (node (ref "S1") (pin "13") (pinfunction "13_13") (pintype "passive"))
      (node (ref "U1") (pin "U23-13") (pinfunction "CSI1D2_U23-13") (pintype "passive"))
    )
    (net (code "114") (name "Net-(U1-CSI1D3)") (class "Default")
      (node (ref "S1") (pin "14") (pinfunction "14_14") (pintype "passive"))
      (node (ref "U1") (pin "U23-14") (pinfunction "CSI1D3_U23-14") (pintype "passive"))
    )
    (net (code "115") (name "Net-(U1-CSI1D4)") (class "Default")
      (node (ref "S1") (pin "15") (pinfunction "15_15") (pintype "passive"))
      (node (ref "U1") (pin "U23-15") (pinfunction "CSI1D4_U23-15") (pintype "passive"))
    )
    (net (code "116") (name "Net-(U1-CSI1D5)") (class "Default")
      (node (ref "S1") (pin "16") (pinfunction "16_16") (pintype "passive"))
      (node (ref "U1") (pin "U23-16") (pinfunction "CSI1D5_U23-16") (pintype "passive"))
    )
    (net (code "117") (name "Net-(U1-CSI1D6)") (class "Default")
      (node (ref "S1") (pin "17") (pinfunction "17_17") (pintype "passive"))
      (node (ref "U1") (pin "U23-17") (pinfunction "CSI1D6_U23-17") (pintype "passive"))
    )
    (net (code "118") (name "Net-(U1-CSI1D7)") (class "Default")
      (node (ref "S1") (pin "18") (pinfunction "18_18") (pintype "passive"))
      (node (ref "U1") (pin "U23-18") (pinfunction "CSI1D7_U23-18") (pintype "passive"))
    )
    (net (code "119") (name "Net-(U1-CSI1HSYNC)") (class "Default")
      (node (ref "S1") (pin "9") (pinfunction "9_9") (pintype "passive"))
      (node (ref "U1") (pin "U23-9") (pinfunction "CSI1HSYNC_U23-9") (pintype "passive"))
    )
    (net (code "120") (name "Net-(U1-CSI1VSYNC)") (class "Default")
      (node (ref "S1") (pin "8") (pinfunction "8_8") (pintype "passive"))
      (node (ref "U1") (pin "U23-8") (pinfunction "CSI1VSYNC_U23-8") (pintype "passive"))
    )
    (net (code "121") (name "Net-(U1-CVBS_OUT)") (class "Default")
      (node (ref "S1") (pin "43") (pinfunction "43_43") (pintype "passive"))
      (node (ref "U1") (pin "U23-43") (pinfunction "CVBS_OUT_U23-43") (pintype "passive"))
    )
    (net (code "122") (name "Net-(U1-FMINL)") (class "Default")
      (node (ref "S1") (pin "21") (pinfunction "21_21") (pintype "passive"))
      (node (ref "U1") (pin "U23-21") (pinfunction "FMINL_U23-21") (pintype "passive"))
    )
    (net (code "123") (name "Net-(U1-FMINR)") (class "Default")
      (node (ref "S1") (pin "23") (pinfunction "23_23") (pintype "passive"))
      (node (ref "U1") (pin "U23-23") (pinfunction "FMINR_U23-23") (pintype "passive"))
    )
    (net (code "124") (name "Net-(U1-GPIOA13)") (class "Default")
      (node (ref "J2") (pin "2") (pinfunction "2_2") (pintype "passive"))
      (node (ref "S1") (pin "38") (pinfunction "38_38") (pintype "passive"))
      (node (ref "U1") (pin "U23-38") (pinfunction "GPIOA13_U23-38") (pintype "passive"))
    )
    (net (code "125") (name "Net-(U1-GPIOA28)") (class "Default")
      (node (ref "S2") (pin "36") (pinfunction "36_36") (pintype "passive"))
      (node (ref "U1") (pin "U24-36") (pinfunction "GPIOA28_U24-36") (pintype "passive"))
    )
    (net (code "126") (name "Net-(U1-GPIOD16)") (class "Default")
      (node (ref "J2") (pin "4") (pinfunction "4_4") (pintype "passive"))
      (node (ref "S1") (pin "46") (pinfunction "46_46") (pintype "passive"))
      (node (ref "U1") (pin "U23-46") (pinfunction "GPIOD16_U23-46") (pintype "passive"))
    )
    (net (code "127") (name "Net-(U1-GPIOD25)") (class "Default")
      (node (ref "J2") (pin "3") (pinfunction "3_3") (pintype "passive"))
      (node (ref "S1") (pin "40") (pinfunction "40_40") (pintype "passive"))
      (node (ref "U1") (pin "U23-40") (pinfunction "GPIOD25_U23-40") (pintype "passive"))
    )
    (net (code "128") (name "Net-(U1-HPL)") (class "Default")
      (node (ref "S1") (pin "45") (pinfunction "45_45") (pintype "passive"))
      (node (ref "U1") (pin "U23-45") (pinfunction "HPL_U23-45") (pintype "passive"))
    )
    (net (code "129") (name "Net-(U1-HPR)") (class "Default")
      (node (ref "S1") (pin "47") (pinfunction "47_47") (pintype "passive"))
      (node (ref "U1") (pin "U23-47") (pinfunction "HPR_U23-47") (pintype "passive"))
    )
    (net (code "130") (name "Net-(U1-HSIC_DQ)") (class "Default")
      (node (ref "S2") (pin "33") (pinfunction "33_33") (pintype "passive"))
      (node (ref "U1") (pin "U24-33") (pinfunction "HSIC_DQ_U24-33") (pintype "passive"))
    )
    (net (code "131") (name "Net-(U1-HSIC_DQS)") (class "Default")
      (node (ref "S2") (pin "35") (pinfunction "35_35") (pintype "passive"))
      (node (ref "U1") (pin "U24-35") (pinfunction "HSIC_DQS_U24-35") (pintype "passive"))
    )
    (net (code "132") (name "Net-(U1-LCD-PIO0{slash}INT)") (class "Default")
      (node (ref "S2") (pin "37") (pinfunction "37_37") (pintype "passive"))
      (node (ref "U1") (pin "U24-37") (pinfunction "LCD-PIO0/INT_U24-37") (pintype "passive"))
    )
    (net (code "133") (name "Net-(U1-LCDCLK)") (class "Default")
      (node (ref "S2") (pin "29") (pinfunction "29_29") (pintype "passive"))
      (node (ref "U1") (pin "U24-29") (pinfunction "LCDCLK_U24-29") (pintype "passive"))
    )
    (net (code "134") (name "Net-(U1-LCDD0)") (class "Default")
      (node (ref "S2") (pin "1") (pinfunction "1_1") (pintype "passive"))
      (node (ref "U1") (pin "U24-1") (pinfunction "LCDD0_U24-1") (pintype "passive"))
    )
    (net (code "135") (name "Net-(U1-LCDD1)") (class "Default")
      (node (ref "S2") (pin "4") (pinfunction "4_4") (pintype "passive"))
      (node (ref "U1") (pin "U24-4") (pinfunction "LCDD1_U24-4") (pintype "power_in"))
    )
    (net (code "136") (name "Net-(U1-LCDD2)") (class "Default")
      (node (ref "S2") (pin "3") (pinfunction "3_3") (pintype "passive"))
      (node (ref "U1") (pin "U24-3") (pinfunction "LCDD2_U24-3") (pintype "power_in"))
    )
    (net (code "137") (name "Net-(U1-LCDD3)") (class "Default")
      (node (ref "S2") (pin "6") (pinfunction "6_6") (pintype "passive"))
      (node (ref "U1") (pin "U24-6") (pinfunction "LCDD3_U24-6") (pintype "power_in"))
    )
    (net (code "138") (name "Net-(U1-LCDD4)") (class "Default")
      (node (ref "S2") (pin "5") (pinfunction "5_5") (pintype "passive"))
      (node (ref "U1") (pin "U24-5") (pinfunction "LCDD4_U24-5") (pintype "power_in"))
    )
    (net (code "139") (name "Net-(U1-LCDD5)") (class "Default")
      (node (ref "S2") (pin "8") (pinfunction "8_8") (pintype "passive"))
      (node (ref "U1") (pin "U24-8") (pinfunction "LCDD5_U24-8") (pintype "power_in"))
    )
    (net (code "140") (name "Net-(U1-LCDD6)") (class "Default")
      (node (ref "S2") (pin "7") (pinfunction "7_7") (pintype "passive"))
      (node (ref "U1") (pin "U24-7") (pinfunction "LCDD6_U24-7") (pintype "power_in"))
    )
    (net (code "141") (name "Net-(U1-LCDD7)") (class "Default")
      (node (ref "S2") (pin "10") (pinfunction "10_10") (pintype "passive"))
      (node (ref "U1") (pin "U24-10") (pinfunction "LCDD7_U24-10") (pintype "passive"))
    )
    (net (code "142") (name "Net-(U1-LCDD8)") (class "Default")
      (node (ref "S2") (pin "12") (pinfunction "12_12") (pintype "passive"))
      (node (ref "U1") (pin "U24-12") (pinfunction "LCDD8_U24-12") (pintype "passive"))
    )
    (net (code "143") (name "Net-(U1-LCDD9)") (class "Default")
      (node (ref "S2") (pin "11") (pinfunction "11_11") (pintype "passive"))
      (node (ref "U1") (pin "U24-11") (pinfunction "LCDD9_U24-11") (pintype "passive"))
    )
    (net (code "144") (name "Net-(U1-LCDD10)") (class "Default")
      (node (ref "S2") (pin "14") (pinfunction "14_14") (pintype "passive"))
      (node (ref "U1") (pin "U24-14") (pinfunction "LCDD10_U24-14") (pintype "passive"))
    )
    (net (code "145") (name "Net-(U1-LCDD11)") (class "Default")
      (node (ref "S2") (pin "13") (pinfunction "13_13") (pintype "passive"))
      (node (ref "U1") (pin "U24-13") (pinfunction "LCDD11_U24-13") (pintype "passive"))
    )
    (net (code "146") (name "Net-(U1-LCDD12)") (class "Default")
      (node (ref "S2") (pin "16") (pinfunction "16_16") (pintype "passive"))
      (node (ref "U1") (pin "U24-16") (pinfunction "LCDD12_U24-16") (pintype "passive"))
    )
    (net (code "147") (name "Net-(U1-LCDD13)") (class "Default")
      (node (ref "S2") (pin "15") (pinfunction "15_15") (pintype "passive"))
      (node (ref "U1") (pin "U24-15") (pinfunction "LCDD13_U24-15") (pintype "passive"))
    )
    (net (code "148") (name "Net-(U1-LCDD14)") (class "Default")
      (node (ref "S2") (pin "18") (pinfunction "18_18") (pintype "passive"))
      (node (ref "U1") (pin "U24-18") (pinfunction "LCDD14_U24-18") (pintype "passive"))
    )
    (net (code "149") (name "Net-(U1-LCDD15)") (class "Default")
      (node (ref "S2") (pin "17") (pinfunction "17_17") (pintype "passive"))
      (node (ref "U1") (pin "U24-17") (pinfunction "LCDD15_U24-17") (pintype "passive"))
    )
    (net (code "150") (name "Net-(U1-LCDD16)") (class "Default")
      (node (ref "S2") (pin "19") (pinfunction "19_19") (pintype "passive"))
      (node (ref "U1") (pin "U24-19") (pinfunction "LCDD16_U24-19") (pintype "passive"))
    )
    (net (code "151") (name "Net-(U1-LCDD17)") (class "Default")
      (node (ref "S2") (pin "22") (pinfunction "22_22") (pintype "passive"))
      (node (ref "U1") (pin "U24-22") (pinfunction "LCDD17_U24-22") (pintype "passive"))
    )
    (net (code "152") (name "Net-(U1-LCDD18)") (class "Default")
      (node (ref "S2") (pin "21") (pinfunction "21_21") (pintype "passive"))
      (node (ref "U1") (pin "U24-21") (pinfunction "LCDD18_U24-21") (pintype "passive"))
    )
    (net (code "153") (name "Net-(U1-LCDD19)") (class "Default")
      (node (ref "S2") (pin "24") (pinfunction "24_24") (pintype "passive"))
      (node (ref "U1") (pin "U24-24") (pinfunction "LCDD19_U24-24") (pintype "passive"))
    )
    (net (code "154") (name "Net-(U1-LCDD20)") (class "Default")
      (node (ref "S2") (pin "23") (pinfunction "23_23") (pintype "passive"))
      (node (ref "U1") (pin "U24-23") (pinfunction "LCDD20_U24-23") (pintype "passive"))
    )
    (net (code "155") (name "Net-(U1-LCDD21)") (class "Default")
      (node (ref "S2") (pin "26") (pinfunction "26_26") (pintype "passive"))
      (node (ref "U1") (pin "U24-26") (pinfunction "LCDD21_U24-26") (pintype "passive"))
    )
    (net (code "156") (name "Net-(U1-LCDD22)") (class "Default")
      (node (ref "S2") (pin "25") (pinfunction "25_25") (pintype "passive"))
      (node (ref "U1") (pin "U24-25") (pinfunction "LCDD22_U24-25") (pintype "passive"))
    )
    (net (code "157") (name "Net-(U1-LCDD23)") (class "Default")
      (node (ref "S2") (pin "28") (pinfunction "28_28") (pintype "passive"))
      (node (ref "U1") (pin "U24-28") (pinfunction "LCDD23_U24-28") (pintype "passive"))
    )
    (net (code "158") (name "Net-(U1-LCDDE)") (class "Default")
      (node (ref "S2") (pin "32") (pinfunction "32_32") (pintype "passive"))
      (node (ref "U1") (pin "U24-32") (pinfunction "LCDDE_U24-32") (pintype "passive"))
    )
    (net (code "159") (name "Net-(U1-LCDHSYNC)") (class "Default")
      (node (ref "S2") (pin "30") (pinfunction "30_30") (pintype "passive"))
      (node (ref "U1") (pin "U24-30") (pinfunction "LCDHSYNC_U24-30") (pintype "passive"))
    )
    (net (code "160") (name "Net-(U1-LCDVSYNC)") (class "Default")
      (node (ref "S2") (pin "27") (pinfunction "27_27") (pintype "passive"))
      (node (ref "U1") (pin "U24-27") (pinfunction "LCDVSYNC_U24-27") (pintype "passive"))
    )
    (net (code "161") (name "Net-(U1-LRADC0)") (class "Default")
      (node (ref "S1") (pin "41") (pinfunction "41_41") (pintype "passive"))
      (node (ref "U1") (pin "U23-41") (pinfunction "LRADC0_U23-41") (pintype "passive"))
    )
    (net (code "162") (name "Net-(U1-PMU-GPIO3)") (class "Default")
      (node (ref "S1") (pin "42") (pinfunction "42_42") (pintype "passive"))
      (node (ref "U1") (pin "U23-42") (pinfunction "PMU-GPIO3_U23-42") (pintype "passive"))
    )
    (net (code "163") (name "Net-(U1-PMU_PWR)") (class "Default")
      (node (ref "S1") (pin "39") (pinfunction "39_39") (pintype "passive"))
      (node (ref "U1") (pin "U23-39") (pinfunction "PMU_PWR_U23-39") (pintype "passive"))
    )
    (net (code "164") (name "Net-(U1-PWM-BL)") (class "Default")
      (node (ref "S2") (pin "31") (pinfunction "31_31") (pintype "passive"))
      (node (ref "U1") (pin "U24-31") (pinfunction "PWM-BL_U24-31") (pintype "passive"))
    )
    (net (code "165") (name "Net-(U1-SDC_CLK)") (class "Default")
      (node (ref "S1") (pin "24") (pinfunction "24_24") (pintype "passive"))
      (node (ref "U1") (pin "U23-24") (pinfunction "SDC_CLK_U23-24") (pintype "passive"))
    )
    (net (code "166") (name "Net-(U1-SDC_CMD)") (class "Default")
      (node (ref "S1") (pin "22") (pinfunction "22_22") (pintype "passive"))
      (node (ref "U1") (pin "U23-22") (pinfunction "SDC_CMD_U23-22") (pintype "passive"))
    )
    (net (code "167") (name "Net-(U1-SDC_D0)") (class "Default")
      (node (ref "S1") (pin "26") (pinfunction "26_26") (pintype "passive"))
      (node (ref "U1") (pin "U23-26") (pinfunction "SDC_D0_U23-26") (pintype "passive"))
    )
    (net (code "168") (name "Net-(U1-SDC_D1)") (class "Default")
      (node (ref "S1") (pin "28") (pinfunction "28_28") (pintype "passive"))
      (node (ref "U1") (pin "U23-28") (pinfunction "SDC_D1_U23-28") (pintype "passive"))
    )
    (net (code "169") (name "Net-(U1-SDC_D2)") (class "Default")
      (node (ref "S1") (pin "30") (pinfunction "30_30") (pintype "passive"))
      (node (ref "U1") (pin "U23-30") (pinfunction "SDC_D2_U23-30") (pintype "passive"))
    )
    (net (code "170") (name "Net-(U1-SDC_D3)") (class "Default")
      (node (ref "S1") (pin "32") (pinfunction "32_32") (pintype "passive"))
      (node (ref "U1") (pin "U23-32") (pinfunction "SDC_D3_U23-32") (pintype "passive"))
    )
    (net (code "171") (name "Net-(U1-SPIO_MISO)") (class "Default")
      (node (ref "S2") (pin "48") (pinfunction "48_48") (pintype "passive"))
      (node (ref "U1") (pin "U24-48") (pinfunction "SPIO_MISO_U24-48") (pintype "passive"))
    )
    (net (code "172") (name "Net-(U1-SPIO_MOSI)") (class "Default")
      (node (ref "S2") (pin "46") (pinfunction "46_46") (pintype "passive"))
      (node (ref "U1") (pin "U24-46") (pinfunction "SPIO_MOSI_U24-46") (pintype "passive"))
    )
    (net (code "173") (name "Net-(U1-SPIO_SCLK)") (class "Default")
      (node (ref "S2") (pin "47") (pinfunction "47_47") (pintype "passive"))
      (node (ref "U1") (pin "U24-47") (pinfunction "SPIO_SCLK_U24-47") (pintype "passive"))
    )
    (net (code "174") (name "Net-(U1-SPIO_SS)") (class "Default")
      (node (ref "S2") (pin "45") (pinfunction "45_45") (pintype "passive"))
      (node (ref "U1") (pin "U24-45") (pinfunction "SPIO_SS_U24-45") (pintype "passive"))
    )
    (net (code "175") (name "Net-(U1-VCC_3V1)") (class "Default")
      (node (ref "S2") (pin "44") (pinfunction "44_44") (pintype "passive"))
      (node (ref "U1") (pin "U24-44") (pinfunction "VCC_3V1_U24-44") (pintype "passive"))
    )
    (net (code "176") (name "Net-(U3-CN1)") (class "Default")
      (node (ref "C7") (pin "1") (pinfunction "1_1") (pintype "passive"))
      (node (ref "U3") (pin "20") (pinfunction "CN1_20") (pintype "passive"))
    )
    (net (code "177") (name "Net-(U3-CN2)") (class "Default")
      (node (ref "C6") (pin "2") (pinfunction "2_2") (pintype "passive"))
      (node (ref "U3") (pin "4") (pinfunction "CN2_4") (pintype "passive"))
    )
    (net (code "178") (name "Net-(U3-CP1)") (class "Default")
      (node (ref "C7") (pin "2") (pinfunction "2_2") (pintype "passive"))
      (node (ref "U3") (pin "18") (pinfunction "CP1_18") (pintype "passive"))
    )
    (net (code "179") (name "Net-(U3-CP2)") (class "Default")
      (node (ref "C6") (pin "1") (pinfunction "1_1") (pintype "passive"))
      (node (ref "U3") (pin "5") (pinfunction "CP2_5") (pintype "passive"))
    )
    (net (code "180") (name "Net-(U3-INN)") (class "Default")
      (node (ref "R3") (pin "2") (pinfunction "2_2") (pintype "passive"))
      (node (ref "U3") (pin "8") (pinfunction "INN_8") (pintype "passive"))
    )
    (net (code "181") (name "Net-(U3-INP)") (class "Default")
      (node (ref "R4") (pin "2") (pinfunction "2_2") (pintype "passive"))
      (node (ref "U3") (pin "9") (pinfunction "INP_9") (pintype "passive"))
    )
    (net (code "182") (name "Net-(U3-PVOUT)") (class "Default")
      (node (ref "C8") (pin "2") (pinfunction "2_2") (pintype "passive"))
      (node (ref "C9") (pin "1") (pinfunction "1_1") (pintype "passive"))
      (node (ref "U3") (pin "13") (pinfunction "PVDD_13") (pintype "passive"))
      (node (ref "U3") (pin "17") (pinfunction "PVDD_17") (pintype "passive"))
      (node (ref "U3") (pin "19") (pinfunction "PVOUT_19") (pintype "passive"))
    )
    (net (code "183") (name "Net-(U3-VON)") (class "Default")
      (node (ref "C11") (pin "1") (pinfunction "1_1") (pintype "passive"))
      (node (ref "J4") (pin "2") (pinfunction "2_2") (pintype "passive"))
      (node (ref "U3") (pin "14") (pinfunction "VON_14") (pintype "passive"))
    )
    (net (code "184") (name "Net-(U3-VOP)") (class "Default")
      (node (ref "C10") (pin "2") (pinfunction "2_2") (pintype "passive"))
      (node (ref "J4") (pin "1") (pinfunction "1_1") (pintype "passive"))
      (node (ref "U3") (pin "16") (pinfunction "VOP_16") (pintype "passive"))
    )
    (net (code "185") (name "Net-(U4-CN1)") (class "Default")
      (node (ref "C15") (pin "1") (pinfunction "1_1") (pintype "passive"))
      (node (ref "U4") (pin "20") (pinfunction "CN1_20") (pintype "passive"))
    )
    (net (code "186") (name "Net-(U4-CN2)") (class "Default")
      (node (ref "C14") (pin "2") (pinfunction "2_2") (pintype "passive"))
      (node (ref "U4") (pin "4") (pinfunction "CN2_4") (pintype "passive"))
    )
    (net (code "187") (name "Net-(U4-CP1)") (class "Default")
      (node (ref "C15") (pin "2") (pinfunction "2_2") (pintype "passive"))
      (node (ref "U4") (pin "18") (pinfunction "CP1_18") (pintype "passive"))
    )
    (net (code "188") (name "Net-(U4-CP2)") (class "Default")
      (node (ref "C14") (pin "1") (pinfunction "1_1") (pintype "passive"))
      (node (ref "U4") (pin "5") (pinfunction "CP2_5") (pintype "passive"))
    )
    (net (code "189") (name "Net-(U4-INN)") (class "Default")
      (node (ref "R6") (pin "2") (pinfunction "2_2") (pintype "passive"))
      (node (ref "U4") (pin "8") (pinfunction "INN_8") (pintype "passive"))
    )
    (net (code "190") (name "Net-(U4-INP)") (class "Default")
      (node (ref "R7") (pin "2") (pinfunction "2_2") (pintype "passive"))
      (node (ref "U4") (pin "9") (pinfunction "INP_9") (pintype "passive"))
    )
    (net (code "191") (name "Net-(U4-PVOUT)") (class "Default")
      (node (ref "C16") (pin "2") (pinfunction "2_2") (pintype "passive"))
      (node (ref "C17") (pin "1") (pinfunction "1_1") (pintype "passive"))
      (node (ref "U4") (pin "13") (pinfunction "PVDD_13") (pintype "passive"))
      (node (ref "U4") (pin "17") (pinfunction "PVDD_17") (pintype "passive"))
      (node (ref "U4") (pin "19") (pinfunction "PVOUT_19") (pintype "passive"))
    )
    (net (code "192") (name "Net-(U4-VON)") (class "Default")
      (node (ref "C19") (pin "1") (pinfunction "1_1") (pintype "passive"))
      (node (ref "J5") (pin "2") (pinfunction "2_2") (pintype "passive"))
      (node (ref "U4") (pin "14") (pinfunction "VON_14") (pintype "passive"))
    )
    (net (code "193") (name "Net-(U4-VOP)") (class "Default")
      (node (ref "C18") (pin "2") (pinfunction "2_2") (pintype "passive"))
      (node (ref "J5") (pin "1") (pinfunction "1_1") (pintype "passive"))
      (node (ref "U4") (pin "16") (pinfunction "VOP_16") (pintype "passive"))
    )
    (net (code "194") (name "unconnected-(CN-A-Pad15)") (class "Default")
      (node (ref "CN-A") (pin "15") (pinfunction "15_15") (pintype "passive"))
    )
    (net (code "195") (name "unconnected-(CN-A-Pad16)") (class "Default")
      (node (ref "CN-A") (pin "16") (pinfunction "16_16") (pintype "passive"))
    )
    (net (code "196") (name "unconnected-(CN-A-Pad19)") (class "Default")
      (node (ref "CN-A") (pin "19") (pinfunction "19_19") (pintype "passive"))
    )
    (net (code "197") (name "unconnected-(CN-A-Pad20)") (class "Default")
      (node (ref "CN-A") (pin "20") (pinfunction "20_20") (pintype "passive"))
    )
    (net (code "198") (name "unconnected-(CN-A-Pad23)") (class "Default")
      (node (ref "CN-A") (pin "23") (pinfunction "23_23") (pintype "passive"))
    )
    (net (code "199") (name "unconnected-(CN-A-Pad24)") (class "Default")
      (node (ref "CN-A") (pin "24") (pinfunction "24_24") (pintype "passive"))
    )
    (net (code "200") (name "unconnected-(CN-A-Pad27)") (class "Default")
      (node (ref "CN-A") (pin "27") (pinfunction "27_27") (pintype "passive"))
    )
    (net (code "201") (name "unconnected-(CN-A-Pad28)") (class "Default")
      (node (ref "CN-A") (pin "28") (pinfunction "28_28") (pintype "passive"))
    )
    (net (code "202") (name "unconnected-(CN-A-Pad34)") (class "Default")
      (node (ref "CN-A") (pin "34") (pinfunction "34_34") (pintype "passive"))
    )
    (net (code "203") (name "unconnected-(CN-B-Pad2)") (class "Default")
      (node (ref "CN-B") (pin "2") (pinfunction "2_2") (pintype "passive"))
    )
    (net (code "204") (name "unconnected-(CN-B-Pad4)") (class "Default")
      (node (ref "CN-B") (pin "4") (pinfunction "4_4") (pintype "passive"))
    )
    (net (code "205") (name "unconnected-(CN-B-Pad6)") (class "Default")
      (node (ref "CN-B") (pin "6") (pinfunction "6_6") (pintype "passive"))
    )
    (net (code "206") (name "unconnected-(CN-B-Pad20)") (class "Default")
      (node (ref "CN-B") (pin "20") (pinfunction "20_20") (pintype "passive"))
    )
    (net (code "207") (name "unconnected-(CN-B-Pad22)") (class "Default")
      (node (ref "CN-B") (pin "22") (pinfunction "22_22") (pintype "passive"))
    )
    (net (code "208") (name "unconnected-(CN-B-Pad24)") (class "Default")
      (node (ref "CN-B") (pin "24") (pinfunction "24_24") (pintype "passive"))
    )
    (net (code "209") (name "unconnected-(CN-B-Pad26)") (class "Default")
      (node (ref "CN-B") (pin "26") (pinfunction "26_26") (pintype "passive"))
    )
    (net (code "210") (name "unconnected-(CN-B-Pad27)") (class "Default")
      (node (ref "CN-B") (pin "27") (pinfunction "27_27") (pintype "passive"))
    )
    (net (code "211") (name "unconnected-(CN-B-Pad28)") (class "Default")
      (node (ref "CN-B") (pin "28") (pinfunction "28_28") (pintype "passive"))
    )
    (net (code "212") (name "unconnected-(CN-B-Pad29)") (class "Default")
      (node (ref "CN-B") (pin "29") (pinfunction "29_29") (pintype "passive"))
    )
    (net (code "213") (name "unconnected-(CN-B-Pad30)") (class "Default")
      (node (ref "CN-B") (pin "30") (pinfunction "30_30") (pintype "passive"))
    )
    (net (code "214") (name "unconnected-(CN-B-Pad31)") (class "Default")
      (node (ref "CN-B") (pin "31") (pinfunction "31_31") (pintype "passive"))
    )
    (net (code "215") (name "unconnected-(CN-B-Pad32)") (class "Default")
      (node (ref "CN-B") (pin "32") (pinfunction "32_32") (pintype "passive"))
    )
    (net (code "216") (name "unconnected-(CN-B-Pad37)") (class "Default")
      (node (ref "CN-B") (pin "37") (pinfunction "37_37") (pintype "passive"))
    )
    (net (code "217") (name "unconnected-(CN-B-Pad38)") (class "Default")
      (node (ref "CN-B") (pin "38") (pinfunction "38_38") (pintype "passive"))
    )
    (net (code "218") (name "unconnected-(J1-AD0-Pad7)") (class "Default")
      (node (ref "J1") (pin "7") (pinfunction "AD0_7") (pintype "passive"))
    )
    (net (code "219") (name "unconnected-(J1-ESD-Pad5)") (class "Default")
      (node (ref "J1") (pin "5") (pinfunction "ESD_5") (pintype "passive"))
    )
    (net (code "220") (name "unconnected-(J1-FSYNC-Pad10)") (class "Default")
      (node (ref "J1") (pin "10") (pinfunction "FSYNC_10") (pintype "passive"))
    )
    (net (code "221") (name "unconnected-(J1-INT-Pad8)") (class "Default")
      (node (ref "J1") (pin "8") (pinfunction "INT_8") (pintype "passive"))
    )
    (net (code "222") (name "unconnected-(J1-SEC-Pad6)") (class "Default")
      (node (ref "J1") (pin "6") (pinfunction "SEC_6") (pintype "passive"))
    )
    (net (code "223") (name "unconnected-(J1-nCS-Pad9)") (class "Default")
      (node (ref "J1") (pin "9") (pinfunction "nCS_9") (pintype "passive"))
    )
    (net (code "224") (name "unconnected-(J8-Pad1)") (class "Default")
      (node (ref "J8") (pin "1") (pinfunction "1_1") (pintype "passive"))
    )
    (net (code "225") (name "unconnected-(U2-VPP-Pad5)") (class "Default")
      (node (ref "U2") (pin "5") (pinfunction "VPP_5") (pintype "passive"))
    )
    (net (code "226") (name "unconnected-(U3-NC-Pad7)") (class "Default")
      (node (ref "U3") (pin "7") (pinfunction "NC_7") (pintype "passive"))
    )
    (net (code "227") (name "unconnected-(U3-NC-Pad11)") (class "Default")
      (node (ref "U3") (pin "11") (pinfunction "NC_11") (pintype "passive"))
    )
    (net (code "228") (name "unconnected-(U3-NC-Pad12)") (class "Default")
      (node (ref "U3") (pin "12") (pinfunction "NC_12") (pintype "passive"))
    )
    (net (code "229") (name "unconnected-(U4-NC-Pad7)") (class "Default")
      (node (ref "U4") (pin "7") (pinfunction "NC_7") (pintype "passive"))
    )
    (net (code "230") (name "unconnected-(U4-NC-Pad11)") (class "Default")
      (node (ref "U4") (pin "11") (pinfunction "NC_11") (pintype "passive"))
    )
    (net (code "231") (name "unconnected-(U4-NC-Pad12)") (class "Default")
      (node (ref "U4") (pin "12") (pinfunction "NC_12") (pintype "passive"))
    )
  )
)
